# EtapaDeControl.net
KiCad netlist of a schematic drawn in EasyEDA
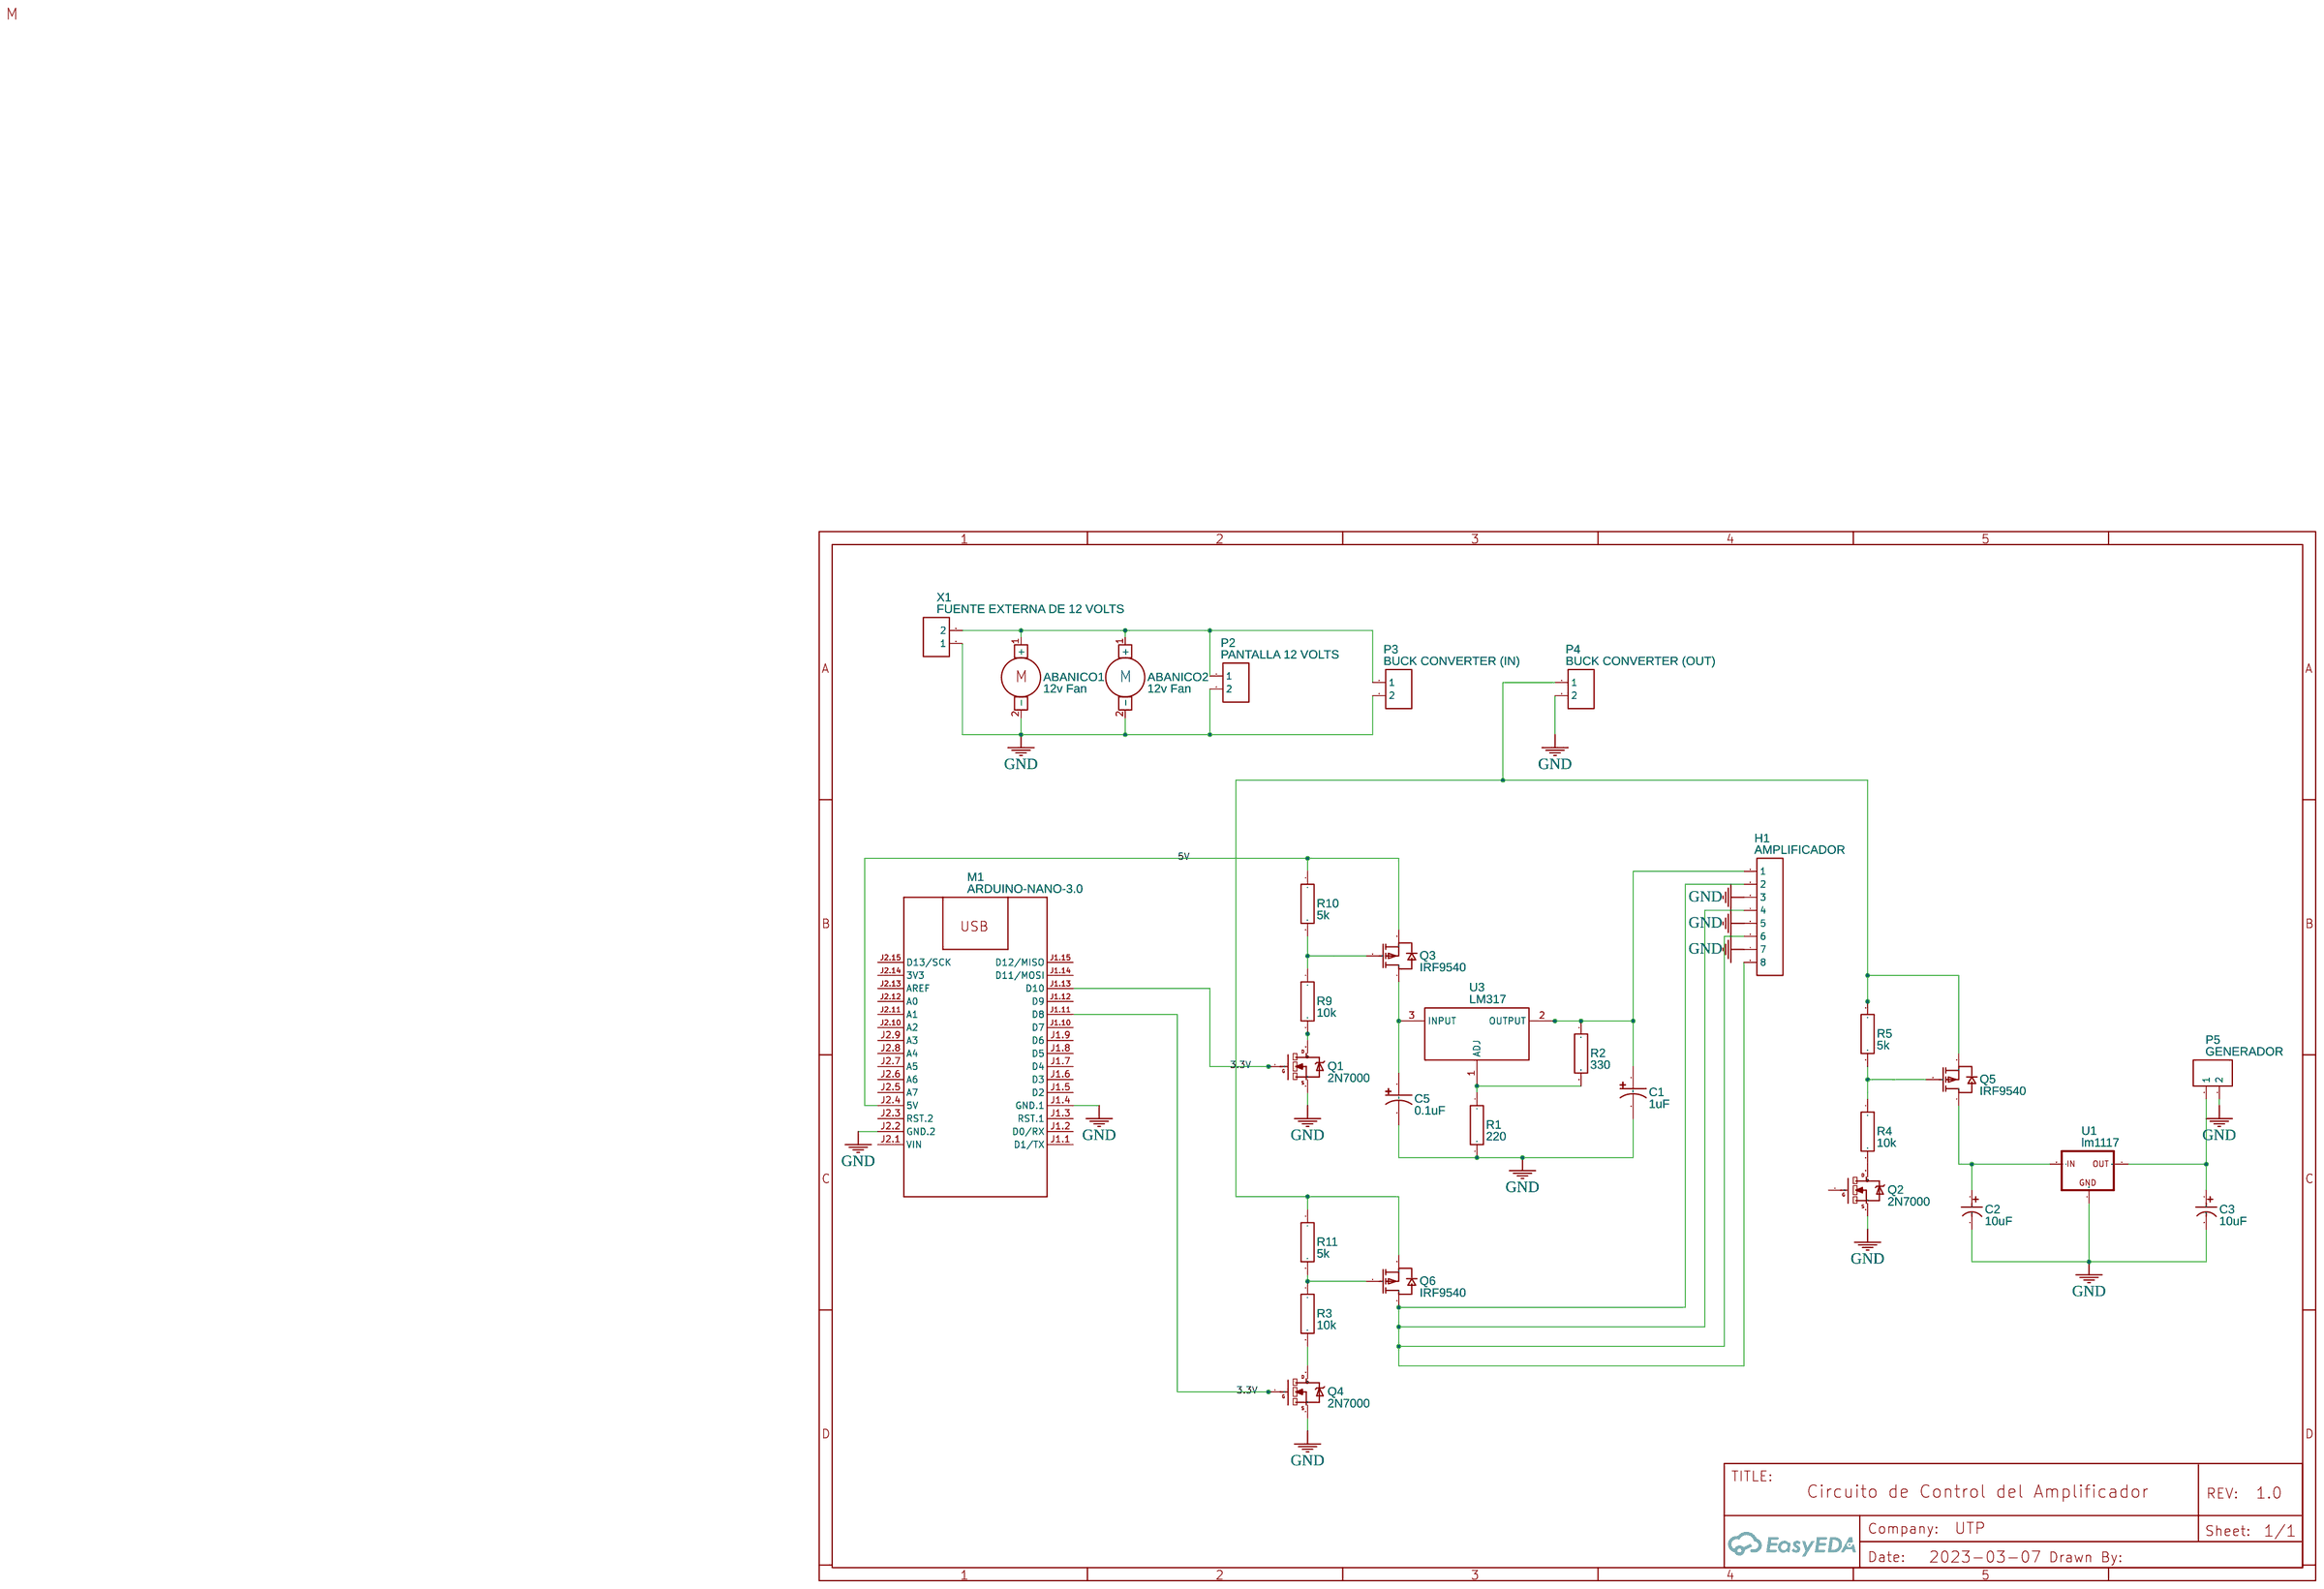
[diagram p0: schematic sheet]

(export (version "E")
  (design (tool "Eeschema 10.0.6"))
  (components
    (comp (ref "ABANICO1") (value "12v Fan") (libsource (lib "") (part "12v Fan_1")))
    (comp (ref "ABANICO2") (value "12v Fan") (libsource (lib "") (part "12v Fan")))
    (comp (ref "C1")
      (value "1uF")
      (fields
        (field (name "BOM_Manufacturer Part") "267M1602105KRA")
        (field (name "BOM_Supplier Part") "C231303")
      )
      (libsource (lib "") (part "267M1602105KRA"))
    )
    (comp (ref "C2")
      (value "10uF")
      (fields
        (field (name "BOM_Manufacturer Part") "VEZ100M1E0405-TRO")
        (field (name "BOM_Supplier Part") "C249759")
      )
      (libsource (lib "") (part "10UF"))
    )
    (comp (ref "C3")
      (value "10uF")
      (fields
        (field (name "BOM_Manufacturer Part") "VEZ100M1E0405-TRO")
        (field (name "BOM_Supplier Part") "C249759")
      )
      (libsource (lib "") (part "10UF"))
    )
    (comp (ref "C5")
      (value "0.1uF")
      (fields
        (field (name "BOM_Manufacturer Part") "267M1602105KRA")
        (field (name "BOM_Supplier Part") "C231303")
      )
      (libsource (lib "") (part "267M1602105KRA"))
    )
    (comp (ref "H1")
      (value "AMPLIFICADOR")
      (fields (field (name "BOM_Supplier Part") "C225505"))
      (libsource (lib "") (part "HDR-F-2.54_1x8"))
    )
    (comp (ref "M1") (value "ARDUINO-NANO-3.0") (libsource (lib "") (part "ARDUINO-NANO-3.0")))
    (comp (ref "P2") (value "PANTALLA 12 VOLTS") (libsource (lib "") (part "CONN-TH_2P-P5.00")))
    (comp (ref "P3") (value "BUCK CONVERTER (IN)") (libsource (lib "") (part "CONN-TH_2P-P5.00")))
    (comp (ref "P4") (value "BUCK CONVERTER (OUT)") (libsource (lib "") (part "CONN-TH_2P-P5.00")))
    (comp (ref "P5") (value "GENERADOR") (libsource (lib "") (part "CONN-TH_2P-P5.00_1")))
    (comp (ref "Q1") (value "2N7000") (libsource (lib "") (part "MOSFET-NCHANNELSMD")))
    (comp (ref "Q2") (value "2N7000") (libsource (lib "") (part "MOSFET-NCHANNELSMD")))
    (comp (ref "Q3")
      (value "IRF9540")
      (fields (field (name "BOM_Supplier Part") "C2622"))
      (libsource (lib "") (part "IRF5210"))
    )
    (comp (ref "Q4") (value "2N7000") (libsource (lib "") (part "MOSFET-NCHANNELSMD")))
    (comp (ref "Q5")
      (value "IRF9540")
      (fields (field (name "BOM_Supplier Part") "C2622"))
      (libsource (lib "") (part "IRF5210"))
    )
    (comp (ref "Q6")
      (value "IRF9540")
      (fields (field (name "BOM_Supplier Part") "C2622"))
      (libsource (lib "") (part "IRF5210"))
    )
    (comp (ref "R1")
      (value "220")
      (fields (field (name "BOM_Manufacturer Part") "RESISTOR-SMD"))
      (libsource (lib "") (part "1,2k"))
    )
    (comp (ref "R2")
      (value "330")
      (fields (field (name "BOM_Manufacturer Part") "RESISTOR-SMD"))
      (libsource (lib "") (part "1,2k"))
    )
    (comp (ref "R3")
      (value "10k")
      (fields (field (name "BOM_Manufacturer Part") "RESISTOR-SMD"))
      (libsource (lib "") (part "1,2k"))
    )
    (comp (ref "R4")
      (value "10k")
      (fields (field (name "BOM_Manufacturer Part") "RESISTOR-SMD"))
      (libsource (lib "") (part "1,2k"))
    )
    (comp (ref "R5")
      (value "5k")
      (fields (field (name "BOM_Manufacturer Part") "RESISTOR-SMD"))
      (libsource (lib "") (part "1,2k"))
    )
    (comp (ref "R9")
      (value "10k")
      (fields (field (name "BOM_Manufacturer Part") "RESISTOR-SMD"))
      (libsource (lib "") (part "1,2k"))
    )
    (comp (ref "R10")
      (value "5k")
      (fields (field (name "BOM_Manufacturer Part") "RESISTOR-SMD"))
      (libsource (lib "") (part "1,2k"))
    )
    (comp (ref "R11")
      (value "5k")
      (fields (field (name "BOM_Manufacturer Part") "RESISTOR-SMD"))
      (libsource (lib "") (part "1,2k"))
    )
    (comp (ref "U1") (value "lm1117") (libsource (lib "") (part "lm1117")))
    (comp (ref "U3")
      (value "LM317")
      (fields
        (field (name "BOM_Manufacturer Part") "Texas Instrument")
        (field (name "BOM_Supplier Part") "296-23224-5-ND")
      )
      (libsource (lib "") (part "LM317"))
    )
    (comp (ref "X1") (value "FUENTE EXTERNA DE 12 VOLTS") (libsource (lib "") (part "CONN-TH_2P-P5.00_2")))
  )
  (nets
    (net (code "1") (name "/3.3V") (class "Default")
      (node (ref "M1") (pin "J1.11") (pinfunction "D8_J1.11") (pintype "bidirectional"))
      (node (ref "M1") (pin "J1.13") (pinfunction "D10_J1.13") (pintype "bidirectional"))
      (node (ref "Q1") (pin "1") (pinfunction "G_1") (pintype "bidirectional"))
      (node (ref "Q4") (pin "1") (pinfunction "G_1") (pintype "bidirectional"))
    )
    (net (code "2") (name "/5V") (class "Default")
      (node (ref "M1") (pin "J2.4") (pinfunction "5V_J2.4") (pintype "bidirectional"))
      (node (ref "Q3") (pin "3") (pinfunction "S_3") (pintype "unspecified"))
      (node (ref "R10") (pin "1") (pinfunction "1_1") (pintype "unspecified"))
    )
    (net (code "3") (name "GND") (class "Default")
      (node (ref "ABANICO1") (pin "2") (pinfunction "-_2") (pintype "unspecified"))
      (node (ref "ABANICO2") (pin "2") (pinfunction "-_2") (pintype "unspecified"))
      (node (ref "C1") (pin "2") (pinfunction "2_2") (pintype "unspecified"))
      (node (ref "C2") (pin "2") (pinfunction "2_2") (pintype "input"))
      (node (ref "C3") (pin "2") (pinfunction "2_2") (pintype "input"))
      (node (ref "C5") (pin "2") (pinfunction "2_2") (pintype "unspecified"))
      (node (ref "H1") (pin "3") (pinfunction "3_3") (pintype "unspecified"))
      (node (ref "H1") (pin "5") (pinfunction "5_5") (pintype "unspecified"))
      (node (ref "H1") (pin "7") (pinfunction "7_7") (pintype "unspecified"))
      (node (ref "M1") (pin "J1.4") (pinfunction "GND.1_J1.4") (pintype "bidirectional"))
      (node (ref "M1") (pin "J2.2") (pinfunction "GND.2_J2.2") (pintype "bidirectional"))
      (node (ref "P2") (pin "2") (pinfunction "2_2") (pintype "unspecified"))
      (node (ref "P3") (pin "2") (pinfunction "2_2") (pintype "unspecified"))
      (node (ref "P4") (pin "2") (pinfunction "2_2") (pintype "unspecified"))
      (node (ref "P5") (pin "2") (pinfunction "2_2") (pintype "unspecified"))
      (node (ref "Q1") (pin "2") (pinfunction "S_2") (pintype "bidirectional"))
      (node (ref "Q2") (pin "2") (pinfunction "S_2") (pintype "bidirectional"))
      (node (ref "Q4") (pin "2") (pinfunction "S_2") (pintype "bidirectional"))
      (node (ref "R1") (pin "2") (pinfunction "2_2") (pintype "unspecified"))
      (node (ref "U1") (pin "1") (pinfunction "GND_1") (pintype "bidirectional"))
      (node (ref "X1") (pin "1") (pinfunction "1_1") (pintype "unspecified"))
    )
    (net (code "4") (name "Net-(ABANICO1-+)") (class "Default")
      (node (ref "ABANICO1") (pin "1") (pinfunction "+_1") (pintype "unspecified"))
      (node (ref "ABANICO2") (pin "1") (pinfunction "+_1") (pintype "unspecified"))
      (node (ref "P2") (pin "1") (pinfunction "1_1") (pintype "unspecified"))
      (node (ref "P3") (pin "1") (pinfunction "1_1") (pintype "unspecified"))
      (node (ref "X1") (pin "2") (pinfunction "2_2") (pintype "unspecified"))
    )
    (net (code "5") (name "Net-(Q1-D)") (class "Default")
      (node (ref "Q1") (pin "3") (pinfunction "D_3") (pintype "bidirectional"))
      (node (ref "R9") (pin "2") (pinfunction "2_2") (pintype "unspecified"))
    )
    (net (code "6") (name "Net-(Q2-D)") (class "Default")
      (node (ref "Q2") (pin "3") (pinfunction "D_3") (pintype "bidirectional"))
      (node (ref "R4") (pin "2") (pinfunction "2_2") (pintype "unspecified"))
    )
    (net (code "7") (name "Net-(Q3-D)") (class "Default")
      (node (ref "C5") (pin "1") (pinfunction "1_1") (pintype "unspecified"))
      (node (ref "Q3") (pin "4") (pinfunction "D_4") (pintype "unspecified"))
      (node (ref "U3") (pin "3") (pinfunction "INPUT_3") (pintype "unspecified"))
    )
    (net (code "8") (name "Net-(Q3-G)") (class "Default")
      (node (ref "Q3") (pin "1") (pinfunction "G_1") (pintype "unspecified"))
      (node (ref "R10") (pin "2") (pinfunction "2_2") (pintype "unspecified"))
      (node (ref "R9") (pin "1") (pinfunction "1_1") (pintype "unspecified"))
    )
    (net (code "9") (name "Net-(Q4-D)") (class "Default")
      (node (ref "Q4") (pin "3") (pinfunction "D_3") (pintype "bidirectional"))
      (node (ref "R3") (pin "2") (pinfunction "2_2") (pintype "unspecified"))
    )
    (net (code "10") (name "Net-(Q5-D)") (class "Default")
      (node (ref "C2") (pin "1") (pinfunction "1_1") (pintype "input"))
      (node (ref "Q5") (pin "4") (pinfunction "D_4") (pintype "unspecified"))
      (node (ref "U1") (pin "3") (pinfunction "IN_3") (pintype "bidirectional"))
    )
    (net (code "11") (name "Net-(Q5-G)") (class "Default")
      (node (ref "Q5") (pin "1") (pinfunction "G_1") (pintype "unspecified"))
      (node (ref "R4") (pin "1") (pinfunction "1_1") (pintype "unspecified"))
      (node (ref "R5") (pin "2") (pinfunction "2_2") (pintype "unspecified"))
    )
    (net (code "12") (name "Net-(Q5-S)") (class "Default")
      (node (ref "P4") (pin "1") (pinfunction "1_1") (pintype "unspecified"))
      (node (ref "Q5") (pin "3") (pinfunction "S_3") (pintype "unspecified"))
      (node (ref "Q6") (pin "3") (pinfunction "S_3") (pintype "unspecified"))
      (node (ref "R11") (pin "1") (pinfunction "1_1") (pintype "unspecified"))
      (node (ref "R5") (pin "1") (pinfunction "1_1") (pintype "unspecified"))
    )
    (net (code "13") (name "Net-(Q6-D)") (class "Default")
      (node (ref "H1") (pin "2") (pinfunction "2_2") (pintype "unspecified"))
      (node (ref "H1") (pin "4") (pinfunction "4_4") (pintype "unspecified"))
      (node (ref "H1") (pin "6") (pinfunction "6_6") (pintype "unspecified"))
      (node (ref "H1") (pin "8") (pinfunction "8_8") (pintype "unspecified"))
      (node (ref "Q6") (pin "4") (pinfunction "D_4") (pintype "unspecified"))
    )
    (net (code "14") (name "Net-(Q6-G)") (class "Default")
      (node (ref "Q6") (pin "1") (pinfunction "G_1") (pintype "unspecified"))
      (node (ref "R11") (pin "2") (pinfunction "2_2") (pintype "unspecified"))
      (node (ref "R3") (pin "1") (pinfunction "1_1") (pintype "unspecified"))
    )
    (net (code "15") (name "Net-(U1-OUT)") (class "Default")
      (node (ref "C3") (pin "1") (pinfunction "1_1") (pintype "input"))
      (node (ref "P5") (pin "1") (pinfunction "1_1") (pintype "unspecified"))
      (node (ref "U1") (pin "2") (pinfunction "OUT_2") (pintype "bidirectional"))
    )
    (net (code "16") (name "Net-(U3-ADJ)") (class "Default")
      (node (ref "R1") (pin "1") (pinfunction "1_1") (pintype "unspecified"))
      (node (ref "R2") (pin "2") (pinfunction "2_2") (pintype "unspecified"))
      (node (ref "U3") (pin "1") (pinfunction "ADJ_1") (pintype "unspecified"))
    )
    (net (code "17") (name "Net-(U3-OUTPUT)") (class "Default")
      (node (ref "C1") (pin "1") (pinfunction "1_1") (pintype "unspecified"))
      (node (ref "H1") (pin "1") (pinfunction "1_1") (pintype "unspecified"))
      (node (ref "R2") (pin "1") (pinfunction "1_1") (pintype "unspecified"))
      (node (ref "U3") (pin "2") (pinfunction "OUTPUT_2") (pintype "unspecified"))
    )
    (net (code "18") (name "unconnected-(M1-3V3-PadJ2.14)") (class "Default")
      (node (ref "M1") (pin "J2.14") (pinfunction "3V3_J2.14") (pintype "bidirectional"))
    )
    (net (code "19") (name "unconnected-(M1-A0-PadJ2.12)") (class "Default")
      (node (ref "M1") (pin "J2.12") (pinfunction "A0_J2.12") (pintype "bidirectional"))
    )
    (net (code "20") (name "unconnected-(M1-A1-PadJ2.11)") (class "Default")
      (node (ref "M1") (pin "J2.11") (pinfunction "A1_J2.11") (pintype "bidirectional"))
    )
    (net (code "21") (name "unconnected-(M1-A2-PadJ2.10)") (class "Default")
      (node (ref "M1") (pin "J2.10") (pinfunction "A2_J2.10") (pintype "bidirectional"))
    )
    (net (code "22") (name "unconnected-(M1-A3-PadJ2.9)") (class "Default")
      (node (ref "M1") (pin "J2.9") (pinfunction "A3_J2.9") (pintype "bidirectional"))
    )
    (net (code "23") (name "unconnected-(M1-A4-PadJ2.8)") (class "Default")
      (node (ref "M1") (pin "J2.8") (pinfunction "A4_J2.8") (pintype "bidirectional"))
    )
    (net (code "24") (name "unconnected-(M1-A5-PadJ2.7)") (class "Default")
      (node (ref "M1") (pin "J2.7") (pinfunction "A5_J2.7") (pintype "bidirectional"))
    )
    (net (code "25") (name "unconnected-(M1-A6-PadJ2.6)") (class "Default")
      (node (ref "M1") (pin "J2.6") (pinfunction "A6_J2.6") (pintype "bidirectional"))
    )
    (net (code "26") (name "unconnected-(M1-A7-PadJ2.5)") (class "Default")
      (node (ref "M1") (pin "J2.5") (pinfunction "A7_J2.5") (pintype "bidirectional"))
    )
    (net (code "27") (name "unconnected-(M1-AREF-PadJ2.13)") (class "Default")
      (node (ref "M1") (pin "J2.13") (pinfunction "AREF_J2.13") (pintype "bidirectional"))
    )
    (net (code "28") (name "unconnected-(M1-D0{slash}RX-PadJ1.2)") (class "Default")
      (node (ref "M1") (pin "J1.2") (pinfunction "D0/RX_J1.2") (pintype "bidirectional"))
    )
    (net (code "29") (name "unconnected-(M1-D1{slash}TX-PadJ1.1)") (class "Default")
      (node (ref "M1") (pin "J1.1") (pinfunction "D1/TX_J1.1") (pintype "bidirectional"))
    )
    (net (code "30") (name "unconnected-(M1-D2-PadJ1.5)") (class "Default")
      (node (ref "M1") (pin "J1.5") (pinfunction "D2_J1.5") (pintype "bidirectional"))
    )
    (net (code "31") (name "unconnected-(M1-D3-PadJ1.6)") (class "Default")
      (node (ref "M1") (pin "J1.6") (pinfunction "D3_J1.6") (pintype "bidirectional"))
    )
    (net (code "32") (name "unconnected-(M1-D4-PadJ1.7)") (class "Default")
      (node (ref "M1") (pin "J1.7") (pinfunction "D4_J1.7") (pintype "bidirectional"))
    )
    (net (code "33") (name "unconnected-(M1-D5-PadJ1.8)") (class "Default")
      (node (ref "M1") (pin "J1.8") (pinfunction "D5_J1.8") (pintype "bidirectional"))
    )
    (net (code "34") (name "unconnected-(M1-D6-PadJ1.9)") (class "Default")
      (node (ref "M1") (pin "J1.9") (pinfunction "D6_J1.9") (pintype "bidirectional"))
    )
    (net (code "35") (name "unconnected-(M1-D7-PadJ1.10)") (class "Default")
      (node (ref "M1") (pin "J1.10") (pinfunction "D7_J1.10") (pintype "bidirectional"))
    )
    (net (code "36") (name "unconnected-(M1-D9-PadJ1.12)") (class "Default")
      (node (ref "M1") (pin "J1.12") (pinfunction "D9_J1.12") (pintype "bidirectional"))
    )
    (net (code "37") (name "unconnected-(M1-D11{slash}MOSI-PadJ1.14)") (class "Default")
      (node (ref "M1") (pin "J1.14") (pinfunction "D11/MOSI_J1.14") (pintype "bidirectional"))
    )
    (net (code "38") (name "unconnected-(M1-D12{slash}MISO-PadJ1.15)") (class "Default")
      (node (ref "M1") (pin "J1.15") (pinfunction "D12/MISO_J1.15") (pintype "bidirectional"))
    )
    (net (code "39") (name "unconnected-(M1-D13{slash}SCK-PadJ2.15)") (class "Default")
      (node (ref "M1") (pin "J2.15") (pinfunction "D13/SCK_J2.15") (pintype "bidirectional"))
    )
    (net (code "40") (name "unconnected-(M1-RST.1-PadJ1.3)") (class "Default")
      (node (ref "M1") (pin "J1.3") (pinfunction "RST.1_J1.3") (pintype "bidirectional"))
    )
    (net (code "41") (name "unconnected-(M1-RST.2-PadJ2.3)") (class "Default")
      (node (ref "M1") (pin "J2.3") (pinfunction "RST.2_J2.3") (pintype "bidirectional"))
    )
    (net (code "42") (name "unconnected-(M1-VIN-PadJ2.1)") (class "Default")
      (node (ref "M1") (pin "J2.1") (pinfunction "VIN_J2.1") (pintype "bidirectional"))
    )
    (net (code "43") (name "unconnected-(Q2-G-Pad1)") (class "Default")
      (node (ref "Q2") (pin "1") (pinfunction "G_1") (pintype "bidirectional"))
    )
  )
)
